# Bank3-4-5_I_O_2.net
KiCad netlist of a schematic drawn in Altium Designer
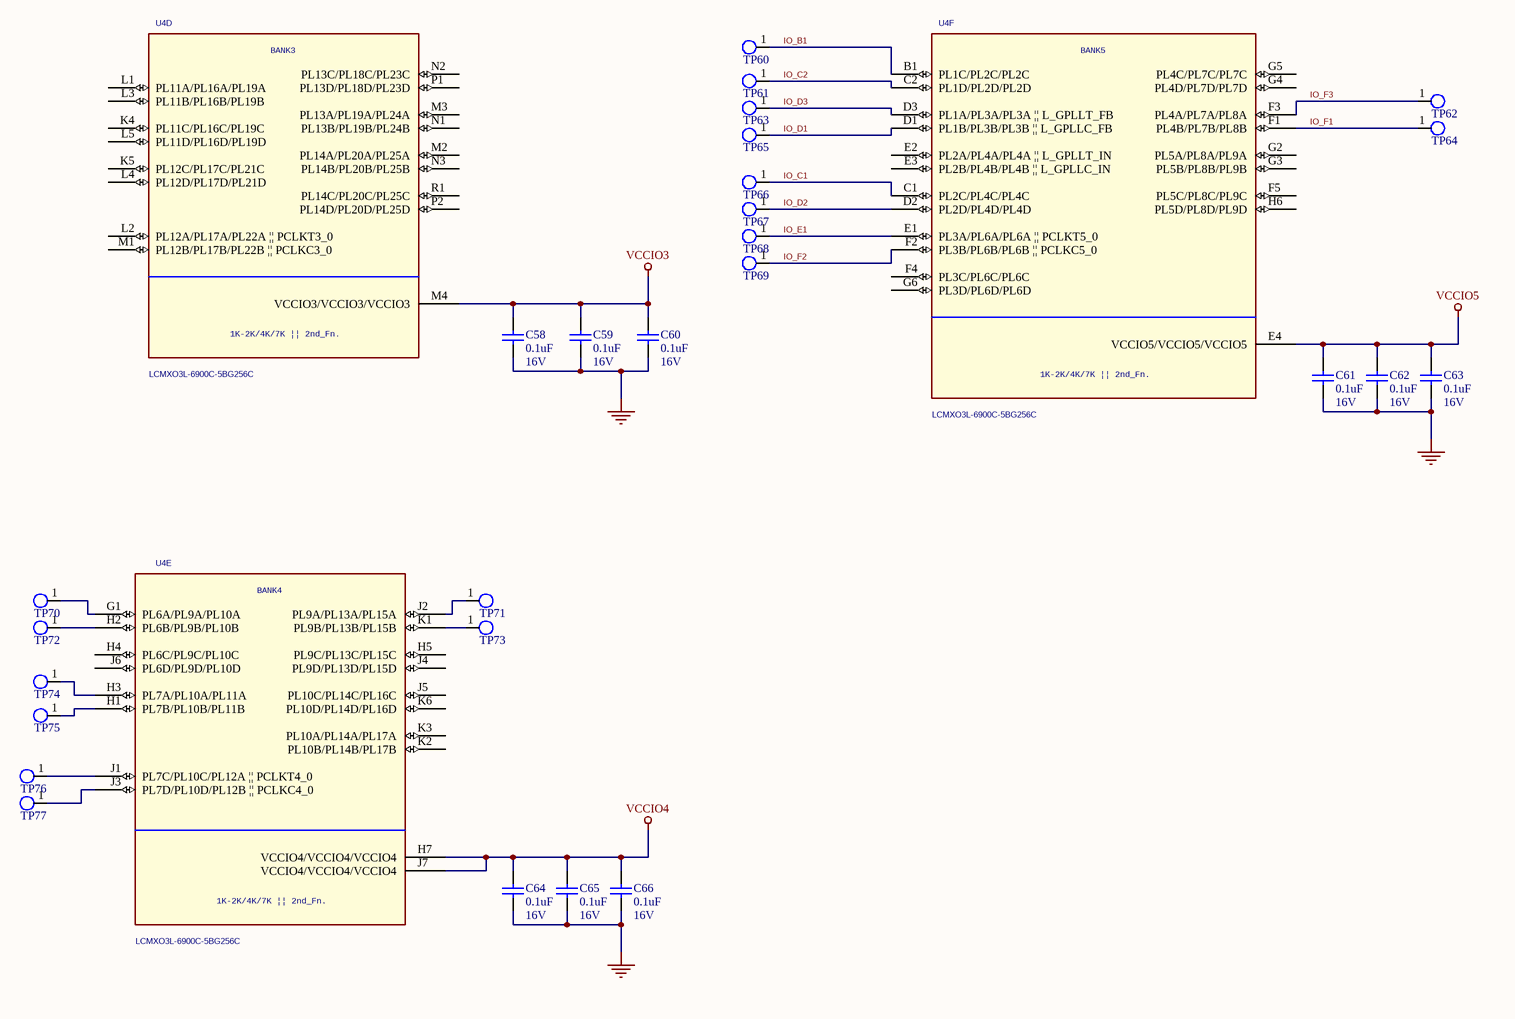
[diagram p0: Bank3-4-5_I_O 2.SchDoc]

(export (version "E")
  (design (tool "Eeschema 10.0.6"))
  (components
    (comp (ref "C58")
      (value "0.1uF")
      (footprint "CAPC1608X87X35ML15T15")
      (description "Ceramic Capacitor 0.1uF 16V +-10% X7R0603")
      (fields
        (field (name "PART NUMBER") "C0603C104M4RACTU")
        (field (name "MANUFACTURER") "Kemet")
        (field (name "VOLTAGE") "16V")
      )
      (libsource (lib "Altium Content Vault") (part "CAP"))
    )
    (comp (ref "C59")
      (value "0.1uF")
      (footprint "CAPC1608X87X35ML15T15")
      (description "Ceramic Capacitor 0.1uF 16V +-10% X7R0603")
      (fields
        (field (name "PART NUMBER") "C0603C104M4RACTU")
        (field (name "MANUFACTURER") "Kemet")
        (field (name "VOLTAGE") "16V")
      )
      (libsource (lib "Altium Content Vault") (part "CAP"))
    )
    (comp (ref "C60")
      (value "0.1uF")
      (footprint "CAPC1608X87X35ML15T15")
      (description "Ceramic Capacitor 0.1uF 16V +-10% X7R0603")
      (fields
        (field (name "PART NUMBER") "C0603C104M4RACTU")
        (field (name "MANUFACTURER") "Kemet")
        (field (name "VOLTAGE") "16V")
      )
      (libsource (lib "Altium Content Vault") (part "CAP"))
    )
    (comp (ref "C61")
      (value "0.1uF")
      (footprint "CAPC1608X87X35ML15T15")
      (description "Ceramic Capacitor 0.1uF 16V +-10% X7R0603")
      (fields
        (field (name "PART NUMBER") "C0603C104M4RACTU")
        (field (name "MANUFACTURER") "Kemet")
        (field (name "VOLTAGE") "16V")
      )
      (libsource (lib "Altium Content Vault") (part "CAP"))
    )
    (comp (ref "C62")
      (value "0.1uF")
      (footprint "CAPC1608X87X35ML15T15")
      (description "Ceramic Capacitor 0.1uF 16V +-10% X7R0603")
      (fields
        (field (name "PART NUMBER") "C0603C104M4RACTU")
        (field (name "MANUFACTURER") "Kemet")
        (field (name "VOLTAGE") "16V")
      )
      (libsource (lib "Altium Content Vault") (part "CAP"))
    )
    (comp (ref "C63")
      (value "0.1uF")
      (footprint "CAPC1608X87X35ML15T15")
      (description "Ceramic Capacitor 0.1uF 16V +-10% X7R0603")
      (fields
        (field (name "PART NUMBER") "C0603C104M4RACTU")
        (field (name "MANUFACTURER") "Kemet")
        (field (name "VOLTAGE") "16V")
      )
      (libsource (lib "Altium Content Vault") (part "CAP"))
    )
    (comp (ref "C64")
      (value "0.1uF")
      (footprint "CAPC1608X87X35ML15T15")
      (description "Ceramic Capacitor 0.1uF 16V +-10% X7R0603")
      (fields
        (field (name "PART NUMBER") "C0603C104M4RACTU")
        (field (name "MANUFACTURER") "Kemet")
        (field (name "VOLTAGE") "16V")
      )
      (libsource (lib "Altium Content Vault") (part "CAP"))
    )
    (comp (ref "C65")
      (value "0.1uF")
      (footprint "CAPC1608X87X35ML15T15")
      (description "Ceramic Capacitor 0.1uF 16V +-10% X7R0603")
      (fields
        (field (name "PART NUMBER") "C0603C104M4RACTU")
        (field (name "MANUFACTURER") "Kemet")
        (field (name "VOLTAGE") "16V")
      )
      (libsource (lib "Altium Content Vault") (part "CAP"))
    )
    (comp (ref "C66")
      (value "0.1uF")
      (footprint "CAPC1608X87X35ML15T15")
      (description "Ceramic Capacitor 0.1uF 16V +-10% X7R0603")
      (fields
        (field (name "PART NUMBER") "C0603C104M4RACTU")
        (field (name "MANUFACTURER") "Kemet")
        (field (name "VOLTAGE") "16V")
      )
      (libsource (lib "Altium Content Vault") (part "CAP"))
    )
    (comp (ref "TP60")
      (value "Test_Point_SMD")
      (footprint "Test_Point_SMD")
      (libsource (lib "Edson") (part "Test_Point_SMD"))
    )
    (comp (ref "TP61")
      (value "Test_Point_SMD")
      (footprint "Test_Point_SMD")
      (libsource (lib "Edson") (part "Test_Point_SMD"))
    )
    (comp (ref "TP62")
      (value "Test_Point_SMD")
      (footprint "Test_Point_SMD")
      (libsource (lib "Edson") (part "Test_Point_SMD"))
    )
    (comp (ref "TP63")
      (value "Test_Point_SMD")
      (footprint "Test_Point_SMD")
      (libsource (lib "Edson") (part "Test_Point_SMD"))
    )
    (comp (ref "TP64")
      (value "Test_Point_SMD")
      (footprint "Test_Point_SMD")
      (libsource (lib "Edson") (part "Test_Point_SMD"))
    )
    (comp (ref "TP65")
      (value "Test_Point_SMD")
      (footprint "Test_Point_SMD")
      (libsource (lib "Edson") (part "Test_Point_SMD"))
    )
    (comp (ref "TP66")
      (value "Test_Point_SMD")
      (footprint "Test_Point_SMD")
      (libsource (lib "Edson") (part "Test_Point_SMD"))
    )
    (comp (ref "TP67")
      (value "Test_Point_SMD")
      (footprint "Test_Point_SMD")
      (libsource (lib "Edson") (part "Test_Point_SMD"))
    )
    (comp (ref "TP68")
      (value "Test_Point_SMD")
      (footprint "Test_Point_SMD")
      (libsource (lib "Edson") (part "Test_Point_SMD"))
    )
    (comp (ref "TP69")
      (value "Test_Point_SMD")
      (footprint "Test_Point_SMD")
      (libsource (lib "Edson") (part "Test_Point_SMD"))
    )
    (comp (ref "TP70")
      (value "Test_Point_SMD")
      (footprint "Test_Point_SMD")
      (libsource (lib "Edson") (part "Test_Point_SMD"))
    )
    (comp (ref "TP71")
      (value "Test_Point_SMD")
      (footprint "Test_Point_SMD")
      (libsource (lib "Edson") (part "Test_Point_SMD"))
    )
    (comp (ref "TP72")
      (value "Test_Point_SMD")
      (footprint "Test_Point_SMD")
      (libsource (lib "Edson") (part "Test_Point_SMD"))
    )
    (comp (ref "TP73")
      (value "Test_Point_SMD")
      (footprint "Test_Point_SMD")
      (libsource (lib "Edson") (part "Test_Point_SMD"))
    )
    (comp (ref "TP74")
      (value "Test_Point_SMD")
      (footprint "Test_Point_SMD")
      (libsource (lib "Edson") (part "Test_Point_SMD"))
    )
    (comp (ref "TP75")
      (value "Test_Point_SMD")
      (footprint "Test_Point_SMD")
      (libsource (lib "Edson") (part "Test_Point_SMD"))
    )
    (comp (ref "TP76")
      (value "Test_Point_SMD")
      (footprint "Test_Point_SMD")
      (libsource (lib "Edson") (part "Test_Point_SMD"))
    )
    (comp (ref "TP77")
      (value "Test_Point_SMD")
      (footprint "Test_Point_SMD")
      (libsource (lib "Edson") (part "Test_Point_SMD"))
    )
    (comp (ref "U4")
      (value "LCMXO3L-6900C-5BG256C")
      (footprint "BGA256C80P16X16_1400X1400X170")
      (description "IC FPGA 6864LUTS 256BGA")
      (fields (field (name "MANUFACTURER") "Lattice semi"))
      (libsource (lib "*") (part "LCMXO3L-1K/2K/4K/7K-BG256"))
    )
  )
  (nets
    (net (code "1") (name "/IO_B1") (class "Default")
      (node (ref "TP60") (pin "1") (pinfunction "TP_1") (pintype "passive"))
      (node (ref "U4") (pin "B1") (pinfunction "PL1C/PL2C/PL2C_B1") (pintype "bidirectional"))
    )
    (net (code "2") (name "/IO_C1") (class "Default")
      (node (ref "TP66") (pin "1") (pinfunction "TP_1") (pintype "passive"))
      (node (ref "U4") (pin "C1") (pinfunction "PL2C/PL4C/PL4C_C1") (pintype "bidirectional"))
    )
    (net (code "3") (name "/IO_C2") (class "Default")
      (node (ref "TP61") (pin "1") (pinfunction "TP_1") (pintype "passive"))
      (node (ref "U4") (pin "C2") (pinfunction "PL1D/PL2D/PL2D_C2") (pintype "bidirectional"))
    )
    (net (code "4") (name "/IO_D1") (class "Default")
      (node (ref "TP65") (pin "1") (pinfunction "TP_1") (pintype "passive"))
      (node (ref "U4") (pin "D1") (pinfunction "PL1B/PL3B/PL3B_Ζ_L_GPLLC_FB_D1") (pintype "bidirectional"))
    )
    (net (code "5") (name "/IO_D2") (class "Default")
      (node (ref "TP67") (pin "1") (pinfunction "TP_1") (pintype "passive"))
      (node (ref "U4") (pin "D2") (pinfunction "PL2D/PL4D/PL4D_D2") (pintype "bidirectional"))
    )
    (net (code "6") (name "/IO_D3") (class "Default")
      (node (ref "TP63") (pin "1") (pinfunction "TP_1") (pintype "passive"))
      (node (ref "U4") (pin "D3") (pinfunction "PL1A/PL3A/PL3A_Ζ_L_GPLLT_FB_D3") (pintype "bidirectional"))
    )
    (net (code "7") (name "/IO_E1") (class "Default")
      (node (ref "TP68") (pin "1") (pinfunction "TP_1") (pintype "passive"))
      (node (ref "U4") (pin "E1") (pinfunction "PL3A/PL6A/PL6A_Ζ_PCLKT5_0_E1") (pintype "bidirectional"))
    )
    (net (code "8") (name "/IO_F1") (class "Default")
      (node (ref "TP64") (pin "1") (pinfunction "TP_1") (pintype "passive"))
      (node (ref "U4") (pin "F1") (pinfunction "PL4B/PL7B/PL8B_F1") (pintype "bidirectional"))
    )
    (net (code "9") (name "/IO_F2") (class "Default")
      (node (ref "TP69") (pin "1") (pinfunction "TP_1") (pintype "passive"))
      (node (ref "U4") (pin "F2") (pinfunction "PL3B/PL6B/PL6B_Ζ_PCLKC5_0_F2") (pintype "bidirectional"))
    )
    (net (code "10") (name "/IO_F3") (class "Default")
      (node (ref "TP62") (pin "1") (pinfunction "TP_1") (pintype "passive"))
      (node (ref "U4") (pin "F3") (pinfunction "PL4A/PL7A/PL8A_F3") (pintype "bidirectional"))
    )
    (net (code "11") (name "GND") (class "Default")
      (node (ref "C58") (pin "2") (pinfunction "2_2") (pintype "passive"))
      (node (ref "C59") (pin "2") (pinfunction "2_2") (pintype "passive"))
      (node (ref "C60") (pin "2") (pinfunction "2_2") (pintype "passive"))
      (node (ref "C61") (pin "2") (pinfunction "2_2") (pintype "passive"))
      (node (ref "C62") (pin "2") (pinfunction "2_2") (pintype "passive"))
      (node (ref "C63") (pin "2") (pinfunction "2_2") (pintype "passive"))
      (node (ref "C64") (pin "2") (pinfunction "2_2") (pintype "passive"))
      (node (ref "C65") (pin "2") (pinfunction "2_2") (pintype "passive"))
      (node (ref "C66") (pin "2") (pinfunction "2_2") (pintype "passive"))
    )
    (net (code "12") (name "Net-(TP70-TP)") (class "Default")
      (node (ref "TP70") (pin "1") (pinfunction "TP_1") (pintype "passive"))
      (node (ref "U4") (pin "G1") (pinfunction "PL6A/PL9A/PL10A_G1") (pintype "bidirectional"))
    )
    (net (code "13") (name "Net-(TP71-TP)") (class "Default")
      (node (ref "TP71") (pin "1") (pinfunction "TP_1") (pintype "passive"))
      (node (ref "U4") (pin "J2") (pinfunction "PL9A/PL13A/PL15A_J2") (pintype "bidirectional"))
    )
    (net (code "14") (name "Net-(TP72-TP)") (class "Default")
      (node (ref "TP72") (pin "1") (pinfunction "TP_1") (pintype "passive"))
      (node (ref "U4") (pin "H2") (pinfunction "PL6B/PL9B/PL10B_H2") (pintype "bidirectional"))
    )
    (net (code "15") (name "Net-(TP73-TP)") (class "Default")
      (node (ref "TP73") (pin "1") (pinfunction "TP_1") (pintype "passive"))
      (node (ref "U4") (pin "K1") (pinfunction "PL9B/PL13B/PL15B_K1") (pintype "bidirectional"))
    )
    (net (code "16") (name "Net-(TP74-TP)") (class "Default")
      (node (ref "TP74") (pin "1") (pinfunction "TP_1") (pintype "passive"))
      (node (ref "U4") (pin "H3") (pinfunction "PL7A/PL10A/PL11A_H3") (pintype "bidirectional"))
    )
    (net (code "17") (name "Net-(TP75-TP)") (class "Default")
      (node (ref "TP75") (pin "1") (pinfunction "TP_1") (pintype "passive"))
      (node (ref "U4") (pin "H1") (pinfunction "PL7B/PL10B/PL11B_H1") (pintype "bidirectional"))
    )
    (net (code "18") (name "Net-(TP76-TP)") (class "Default")
      (node (ref "TP76") (pin "1") (pinfunction "TP_1") (pintype "passive"))
      (node (ref "U4") (pin "J1") (pinfunction "PL7C/PL10C/PL12A_Ζ_PCLKT4_0_J1") (pintype "bidirectional"))
    )
    (net (code "19") (name "Net-(TP77-TP)") (class "Default")
      (node (ref "TP77") (pin "1") (pinfunction "TP_1") (pintype "passive"))
      (node (ref "U4") (pin "J3") (pinfunction "PL7D/PL10D/PL12B_Ζ_PCLKC4_0_J3") (pintype "bidirectional"))
    )
    (net (code "20") (name "VCCIO3") (class "Default")
      (node (ref "C58") (pin "1") (pinfunction "1_1") (pintype "passive"))
      (node (ref "C59") (pin "1") (pinfunction "1_1") (pintype "passive"))
      (node (ref "C60") (pin "1") (pinfunction "1_1") (pintype "passive"))
      (node (ref "U4") (pin "M4") (pinfunction "VCCIO3/VCCIO3/VCCIO3_M4") (pintype "power_in"))
    )
    (net (code "21") (name "VCCIO4") (class "Default")
      (node (ref "C64") (pin "1") (pinfunction "1_1") (pintype "passive"))
      (node (ref "C65") (pin "1") (pinfunction "1_1") (pintype "passive"))
      (node (ref "C66") (pin "1") (pinfunction "1_1") (pintype "passive"))
      (node (ref "U4") (pin "H7") (pinfunction "VCCIO4/VCCIO4/VCCIO4_H7") (pintype "power_in"))
      (node (ref "U4") (pin "J7") (pinfunction "VCCIO4/VCCIO4/VCCIO4_J7") (pintype "power_in"))
    )
    (net (code "22") (name "VCCIO5") (class "Default")
      (node (ref "C61") (pin "1") (pinfunction "1_1") (pintype "passive"))
      (node (ref "C62") (pin "1") (pinfunction "1_1") (pintype "passive"))
      (node (ref "C63") (pin "1") (pinfunction "1_1") (pintype "passive"))
      (node (ref "U4") (pin "E4") (pinfunction "VCCIO5/VCCIO5/VCCIO5_E4") (pintype "power_in"))
    )
    (net (code "23") (name "unconnected-(U4D-PL11A{slash}PL16A{slash}PL19A-PadL1)") (class "Default")
      (node (ref "U4") (pin "L1") (pinfunction "PL11A/PL16A/PL19A_L1") (pintype "bidirectional"))
    )
    (net (code "24") (name "unconnected-(U4D-PL11B{slash}PL16B{slash}PL19B-PadL3)") (class "Default")
      (node (ref "U4") (pin "L3") (pinfunction "PL11B/PL16B/PL19B_L3") (pintype "bidirectional"))
    )
    (net (code "25") (name "unconnected-(U4D-PL11C{slash}PL16C{slash}PL19C-PadK4)") (class "Default")
      (node (ref "U4") (pin "K4") (pinfunction "PL11C/PL16C/PL19C_K4") (pintype "bidirectional"))
    )
    (net (code "26") (name "unconnected-(U4D-PL11D{slash}PL16D{slash}PL19D-PadL5)") (class "Default")
      (node (ref "U4") (pin "L5") (pinfunction "PL11D/PL16D/PL19D_L5") (pintype "bidirectional"))
    )
    (net (code "27") (name "unconnected-(U4D-PL12A{slash}PL17A{slash}PL22A_Ζ_PCLKT3_0-PadL2)") (class "Default")
      (node (ref "U4") (pin "L2") (pinfunction "PL12A/PL17A/PL22A_Ζ_PCLKT3_0_L2") (pintype "bidirectional"))
    )
    (net (code "28") (name "unconnected-(U4D-PL12B{slash}PL17B{slash}PL22B_Ζ_PCLKC3_0-PadM1)") (class "Default")
      (node (ref "U4") (pin "M1") (pinfunction "PL12B/PL17B/PL22B_Ζ_PCLKC3_0_M1") (pintype "bidirectional"))
    )
    (net (code "29") (name "unconnected-(U4D-PL12C{slash}PL17C{slash}PL21C-PadK5)") (class "Default")
      (node (ref "U4") (pin "K5") (pinfunction "PL12C/PL17C/PL21C_K5") (pintype "bidirectional"))
    )
    (net (code "30") (name "unconnected-(U4D-PL12D{slash}PL17D{slash}PL21D-PadL4)") (class "Default")
      (node (ref "U4") (pin "L4") (pinfunction "PL12D/PL17D/PL21D_L4") (pintype "bidirectional"))
    )
    (net (code "31") (name "unconnected-(U4D-PL13A{slash}PL19A{slash}PL24A-PadM3)") (class "Default")
      (node (ref "U4") (pin "M3") (pinfunction "PL13A/PL19A/PL24A_M3") (pintype "bidirectional"))
    )
    (net (code "32") (name "unconnected-(U4D-PL13B{slash}PL19B{slash}PL24B-PadN1)") (class "Default")
      (node (ref "U4") (pin "N1") (pinfunction "PL13B/PL19B/PL24B_N1") (pintype "bidirectional"))
    )
    (net (code "33") (name "unconnected-(U4D-PL13C{slash}PL18C{slash}PL23C-PadN2)") (class "Default")
      (node (ref "U4") (pin "N2") (pinfunction "PL13C/PL18C/PL23C_N2") (pintype "bidirectional"))
    )
    (net (code "34") (name "unconnected-(U4D-PL13D{slash}PL18D{slash}PL23D-PadP1)") (class "Default")
      (node (ref "U4") (pin "P1") (pinfunction "PL13D/PL18D/PL23D_P1") (pintype "bidirectional"))
    )
    (net (code "35") (name "unconnected-(U4D-PL14A{slash}PL20A{slash}PL25A-PadM2)") (class "Default")
      (node (ref "U4") (pin "M2") (pinfunction "PL14A/PL20A/PL25A_M2") (pintype "bidirectional"))
    )
    (net (code "36") (name "unconnected-(U4D-PL14B{slash}PL20B{slash}PL25B-PadN3)") (class "Default")
      (node (ref "U4") (pin "N3") (pinfunction "PL14B/PL20B/PL25B_N3") (pintype "bidirectional"))
    )
    (net (code "37") (name "unconnected-(U4D-PL14C{slash}PL20C{slash}PL25C-PadR1)") (class "Default")
      (node (ref "U4") (pin "R1") (pinfunction "PL14C/PL20C/PL25C_R1") (pintype "bidirectional"))
    )
    (net (code "38") (name "unconnected-(U4D-PL14D{slash}PL20D{slash}PL25D-PadP2)") (class "Default")
      (node (ref "U4") (pin "P2") (pinfunction "PL14D/PL20D/PL25D_P2") (pintype "bidirectional"))
    )
    (net (code "39") (name "unconnected-(U4E-PL6C{slash}PL9C{slash}PL10C-PadH4)") (class "Default")
      (node (ref "U4") (pin "H4") (pinfunction "PL6C/PL9C/PL10C_H4") (pintype "bidirectional"))
    )
    (net (code "40") (name "unconnected-(U4E-PL6D{slash}PL9D{slash}PL10D-PadJ6)") (class "Default")
      (node (ref "U4") (pin "J6") (pinfunction "PL6D/PL9D/PL10D_J6") (pintype "bidirectional"))
    )
    (net (code "41") (name "unconnected-(U4E-PL9C{slash}PL13C{slash}PL15C-PadH5)") (class "Default")
      (node (ref "U4") (pin "H5") (pinfunction "PL9C/PL13C/PL15C_H5") (pintype "bidirectional"))
    )
    (net (code "42") (name "unconnected-(U4E-PL9D{slash}PL13D{slash}PL15D-PadJ4)") (class "Default")
      (node (ref "U4") (pin "J4") (pinfunction "PL9D/PL13D/PL15D_J4") (pintype "bidirectional"))
    )
    (net (code "43") (name "unconnected-(U4E-PL10A{slash}PL14A{slash}PL17A-PadK3)") (class "Default")
      (node (ref "U4") (pin "K3") (pinfunction "PL10A/PL14A/PL17A_K3") (pintype "bidirectional"))
    )
    (net (code "44") (name "unconnected-(U4E-PL10B{slash}PL14B{slash}PL17B-PadK2)") (class "Default")
      (node (ref "U4") (pin "K2") (pinfunction "PL10B/PL14B/PL17B_K2") (pintype "bidirectional"))
    )
    (net (code "45") (name "unconnected-(U4E-PL10C{slash}PL14C{slash}PL16C-PadJ5)") (class "Default")
      (node (ref "U4") (pin "J5") (pinfunction "PL10C/PL14C/PL16C_J5") (pintype "bidirectional"))
    )
    (net (code "46") (name "unconnected-(U4E-PL10D{slash}PL14D{slash}PL16D-PadK6)") (class "Default")
      (node (ref "U4") (pin "K6") (pinfunction "PL10D/PL14D/PL16D_K6") (pintype "bidirectional"))
    )
    (net (code "47") (name "unconnected-(U4F-PL2A{slash}PL4A{slash}PL4A_Ζ_L_GPLLT_IN-PadE2)") (class "Default")
      (node (ref "U4") (pin "E2") (pinfunction "PL2A/PL4A/PL4A_Ζ_L_GPLLT_IN_E2") (pintype "bidirectional"))
    )
    (net (code "48") (name "unconnected-(U4F-PL2B{slash}PL4B{slash}PL4B_Ζ_L_GPLLC_IN-PadE3)") (class "Default")
      (node (ref "U4") (pin "E3") (pinfunction "PL2B/PL4B/PL4B_Ζ_L_GPLLC_IN_E3") (pintype "bidirectional"))
    )
    (net (code "49") (name "unconnected-(U4F-PL3C{slash}PL6C{slash}PL6C-PadF4)") (class "Default")
      (node (ref "U4") (pin "F4") (pinfunction "PL3C/PL6C/PL6C_F4") (pintype "bidirectional"))
    )
    (net (code "50") (name "unconnected-(U4F-PL3D{slash}PL6D{slash}PL6D-PadG6)") (class "Default")
      (node (ref "U4") (pin "G6") (pinfunction "PL3D/PL6D/PL6D_G6") (pintype "bidirectional"))
    )
    (net (code "51") (name "unconnected-(U4F-PL4C{slash}PL7C{slash}PL7C-PadG5)") (class "Default")
      (node (ref "U4") (pin "G5") (pinfunction "PL4C/PL7C/PL7C_G5") (pintype "bidirectional"))
    )
    (net (code "52") (name "unconnected-(U4F-PL4D{slash}PL7D{slash}PL7D-PadG4)") (class "Default")
      (node (ref "U4") (pin "G4") (pinfunction "PL4D/PL7D/PL7D_G4") (pintype "bidirectional"))
    )
    (net (code "53") (name "unconnected-(U4F-PL5A{slash}PL8A{slash}PL9A-PadG2)") (class "Default")
      (node (ref "U4") (pin "G2") (pinfunction "PL5A/PL8A/PL9A_G2") (pintype "bidirectional"))
    )
    (net (code "54") (name "unconnected-(U4F-PL5B{slash}PL8B{slash}PL9B-PadG3)") (class "Default")
      (node (ref "U4") (pin "G3") (pinfunction "PL5B/PL8B/PL9B_G3") (pintype "bidirectional"))
    )
    (net (code "55") (name "unconnected-(U4F-PL5C{slash}PL8C{slash}PL9C-PadF5)") (class "Default")
      (node (ref "U4") (pin "F5") (pinfunction "PL5C/PL8C/PL9C_F5") (pintype "bidirectional"))
    )
    (net (code "56") (name "unconnected-(U4F-PL5D{slash}PL8D{slash}PL9D-PadH6)") (class "Default")
      (node (ref "U4") (pin "H6") (pinfunction "PL5D/PL8D/PL9D_H6") (pintype "bidirectional"))
    )
  )
)
